# StreamDeck.net
KiCad netlist of a schematic drawn in EAGLE
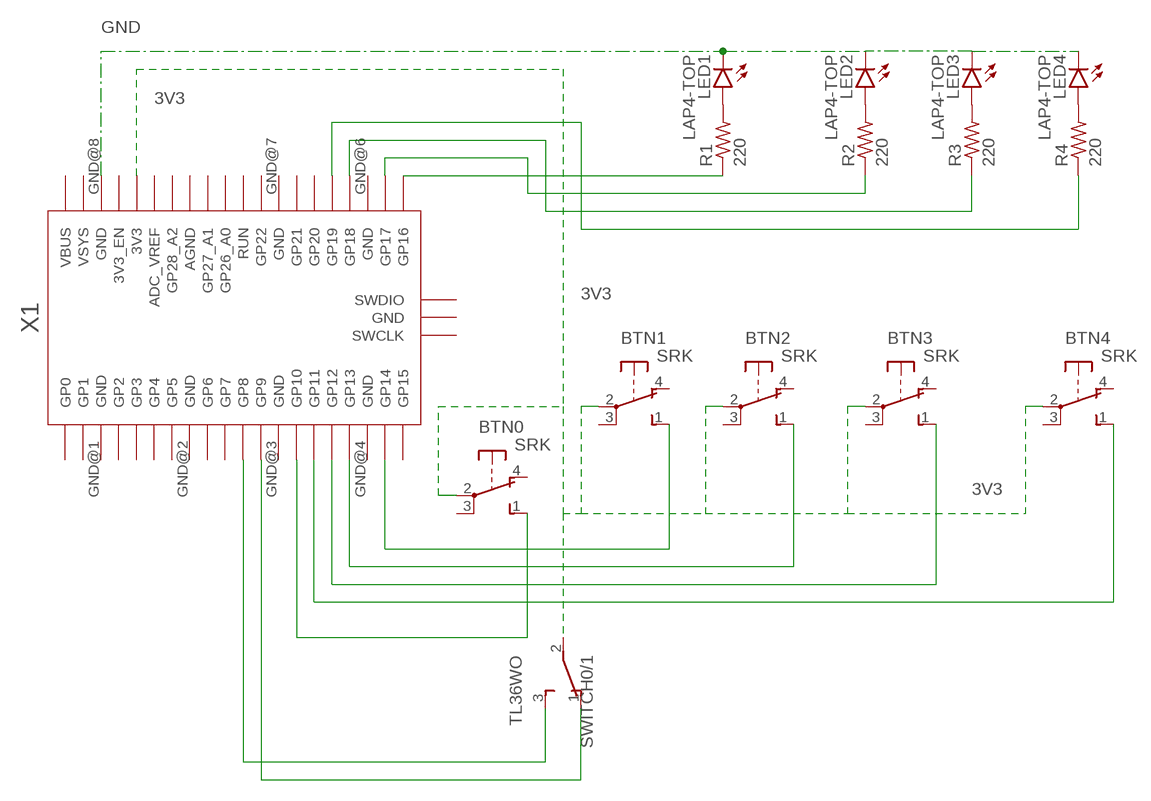
[diagram p0: schematic, sheet 1]

(export (version "E")
  (design (tool "Eeschema 10.0.6"))
  (components
    (comp (ref "BTN0")
      (value "SRK")
      (footprint "eagle-import:SRK")
      (libsource (lib "eagle-import") (part "SRK"))
    )
    (comp (ref "BTN1")
      (value "SRK")
      (footprint "eagle-import:SRK")
      (libsource (lib "eagle-import") (part "SRK"))
    )
    (comp (ref "BTN2")
      (value "SRK")
      (footprint "eagle-import:SRK")
      (libsource (lib "eagle-import") (part "SRK"))
    )
    (comp (ref "BTN3")
      (value "SRK")
      (footprint "eagle-import:SRK")
      (libsource (lib "eagle-import") (part "SRK"))
    )
    (comp (ref "BTN4")
      (value "SRK")
      (footprint "eagle-import:SRK")
      (libsource (lib "eagle-import") (part "SRK"))
    )
    (comp (ref "LED1")
      (value "LAP4-TOP")
      (footprint "eagle-import:P47F-TOP")
      (libsource (lib "eagle-import") (part "P4-TOPLA"))
    )
    (comp (ref "LED2")
      (value "LAP4-TOP")
      (footprint "eagle-import:P47F-TOP")
      (libsource (lib "eagle-import") (part "P4-TOPLA"))
    )
    (comp (ref "LED3")
      (value "LAP4-TOP")
      (footprint "eagle-import:P47F-TOP")
      (libsource (lib "eagle-import") (part "P4-TOPLA"))
    )
    (comp (ref "LED4")
      (value "LAP4-TOP")
      (footprint "eagle-import:P47F-TOP")
      (libsource (lib "eagle-import") (part "P4-TOPLA"))
    )
    (comp (ref "R1")
      (value "220")
      (footprint "eagle-import:0204_5")
      (libsource (lib "eagle-import") (part "R-US_0204/5"))
    )
    (comp (ref "R2")
      (value "220")
      (footprint "eagle-import:0204_5")
      (libsource (lib "eagle-import") (part "R-US_0204/5"))
    )
    (comp (ref "R3")
      (value "220")
      (footprint "eagle-import:0204_5")
      (libsource (lib "eagle-import") (part "R-US_0204/5"))
    )
    (comp (ref "R4")
      (value "220")
      (footprint "eagle-import:0204_5")
      (libsource (lib "eagle-import") (part "R-US_0204/5"))
    )
    (comp (ref "SWITCH0/1")
      (value "TL36WO")
      (footprint "eagle-import:TL3XWO")
      (libsource (lib "eagle-import") (part "TL36WO"))
    )
    (comp (ref "X1")
      (value "RPI_PICO_IG-SMD")
      (footprint "eagle-import:RPI_PICO")
      (libsource (lib "eagle-import") (part "RPI_PICO_IG-SMD"))
    )
  )
  (nets
    (net (code "1") (name "/3V3") (class "Default")
      (node (ref "BTN0") (pin "2") (pinfunction "P_2") (pintype "passive"))
      (node (ref "BTN1") (pin "2") (pinfunction "P_2") (pintype "passive"))
      (node (ref "BTN2") (pin "2") (pinfunction "P_2") (pintype "passive"))
      (node (ref "BTN3") (pin "2") (pinfunction "P_2") (pintype "passive"))
      (node (ref "BTN4") (pin "2") (pinfunction "P_2") (pintype "passive"))
      (node (ref "SWITCH0/1") (pin "2") (pinfunction "P_2") (pintype "passive"))
      (node (ref "X1") (pin "3V3") (pinfunction "3V3_3V3") (pintype "bidirectional"))
    )
    (net (code "2") (name "/GND") (class "Default")
      (node (ref "LED1") (pin "C") (pinfunction "C_C") (pintype "passive"))
      (node (ref "LED2") (pin "C") (pinfunction "C_C") (pintype "passive"))
      (node (ref "LED3") (pin "C") (pinfunction "C_C") (pintype "passive"))
      (node (ref "LED4") (pin "C") (pinfunction "C_C") (pintype "passive"))
      (node (ref "X1") (pin "GND@8") (pinfunction "GND_GND@8") (pintype "bidirectional"))
    )
    (net (code "3") (name "Net-(BTN0-S)") (class "Default")
      (node (ref "BTN0") (pin "1") (pinfunction "S_1") (pintype "passive"))
      (node (ref "X1") (pin "GP10") (pinfunction "GP10_GP10") (pintype "bidirectional"))
    )
    (net (code "4") (name "Net-(BTN1-S)") (class "Default")
      (node (ref "BTN1") (pin "1") (pinfunction "S_1") (pintype "passive"))
      (node (ref "X1") (pin "GP14") (pinfunction "GP14_GP14") (pintype "bidirectional"))
    )
    (net (code "5") (name "Net-(BTN2-S)") (class "Default")
      (node (ref "BTN2") (pin "1") (pinfunction "S_1") (pintype "passive"))
      (node (ref "X1") (pin "GP13") (pinfunction "GP13_GP13") (pintype "bidirectional"))
    )
    (net (code "6") (name "Net-(BTN3-S)") (class "Default")
      (node (ref "BTN3") (pin "1") (pinfunction "S_1") (pintype "passive"))
      (node (ref "X1") (pin "GP12") (pinfunction "GP12_GP12") (pintype "bidirectional"))
    )
    (net (code "7") (name "Net-(BTN4-S)") (class "Default")
      (node (ref "BTN4") (pin "1") (pinfunction "S_1") (pintype "passive"))
      (node (ref "X1") (pin "GP11") (pinfunction "GP11_GP11") (pintype "bidirectional"))
    )
    (net (code "8") (name "Net-(LED1-PadA)") (class "Default")
      (node (ref "LED1") (pin "A") (pinfunction "A_A") (pintype "passive"))
      (node (ref "R1") (pin "2") (pinfunction "2_2") (pintype "passive"))
    )
    (net (code "9") (name "Net-(LED2-PadA)") (class "Default")
      (node (ref "LED2") (pin "A") (pinfunction "A_A") (pintype "passive"))
      (node (ref "R2") (pin "2") (pinfunction "2_2") (pintype "passive"))
    )
    (net (code "10") (name "Net-(LED3-PadA)") (class "Default")
      (node (ref "LED3") (pin "A") (pinfunction "A_A") (pintype "passive"))
      (node (ref "R3") (pin "2") (pinfunction "2_2") (pintype "passive"))
    )
    (net (code "11") (name "Net-(LED4-PadA)") (class "Default")
      (node (ref "LED4") (pin "A") (pinfunction "A_A") (pintype "passive"))
      (node (ref "R4") (pin "2") (pinfunction "2_2") (pintype "passive"))
    )
    (net (code "12") (name "Net-(R1-Pad1)") (class "Default")
      (node (ref "R1") (pin "1") (pinfunction "1_1") (pintype "passive"))
      (node (ref "X1") (pin "GP16") (pinfunction "GP16_GP16") (pintype "bidirectional"))
    )
    (net (code "13") (name "Net-(R2-Pad1)") (class "Default")
      (node (ref "R2") (pin "1") (pinfunction "1_1") (pintype "passive"))
      (node (ref "X1") (pin "GP17") (pinfunction "GP17_GP17") (pintype "bidirectional"))
    )
    (net (code "14") (name "Net-(R3-Pad1)") (class "Default")
      (node (ref "R3") (pin "1") (pinfunction "1_1") (pintype "passive"))
      (node (ref "X1") (pin "GP18") (pinfunction "GP18_GP18") (pintype "bidirectional"))
    )
    (net (code "15") (name "Net-(R4-Pad1)") (class "Default")
      (node (ref "R4") (pin "1") (pinfunction "1_1") (pintype "passive"))
      (node (ref "X1") (pin "GP19") (pinfunction "GP19_GP19") (pintype "bidirectional"))
    )
    (net (code "16") (name "Net-(SWITCH0/1-O)") (class "Default")
      (node (ref "SWITCH0/1") (pin "1") (pinfunction "O_1") (pintype "passive"))
      (node (ref "X1") (pin "GP9") (pinfunction "GP9_GP9") (pintype "bidirectional"))
    )
    (net (code "17") (name "Net-(SWITCH0/1-S)") (class "Default")
      (node (ref "SWITCH0/1") (pin "3") (pinfunction "S_3") (pintype "passive"))
      (node (ref "X1") (pin "GP8") (pinfunction "GP8_GP8") (pintype "bidirectional"))
    )
    (net (code "18") (name "unconnected-(BTN0-O-Pad4)") (class "Default")
      (node (ref "BTN0") (pin "4") (pinfunction "O_4") (pintype "passive"))
    )
    (net (code "19") (name "unconnected-(BTN0-P-Pad3)") (class "Default")
      (node (ref "BTN0") (pin "3") (pinfunction "P_3") (pintype "passive"))
    )
    (net (code "20") (name "unconnected-(BTN1-O-Pad4)") (class "Default")
      (node (ref "BTN1") (pin "4") (pinfunction "O_4") (pintype "passive"))
    )
    (net (code "21") (name "unconnected-(BTN1-P-Pad3)") (class "Default")
      (node (ref "BTN1") (pin "3") (pinfunction "P_3") (pintype "passive"))
    )
    (net (code "22") (name "unconnected-(BTN2-O-Pad4)") (class "Default")
      (node (ref "BTN2") (pin "4") (pinfunction "O_4") (pintype "passive"))
    )
    (net (code "23") (name "unconnected-(BTN2-P-Pad3)") (class "Default")
      (node (ref "BTN2") (pin "3") (pinfunction "P_3") (pintype "passive"))
    )
    (net (code "24") (name "unconnected-(BTN3-O-Pad4)") (class "Default")
      (node (ref "BTN3") (pin "4") (pinfunction "O_4") (pintype "passive"))
    )
    (net (code "25") (name "unconnected-(BTN3-P-Pad3)") (class "Default")
      (node (ref "BTN3") (pin "3") (pinfunction "P_3") (pintype "passive"))
    )
    (net (code "26") (name "unconnected-(BTN4-O-Pad4)") (class "Default")
      (node (ref "BTN4") (pin "4") (pinfunction "O_4") (pintype "passive"))
    )
    (net (code "27") (name "unconnected-(BTN4-P-Pad3)") (class "Default")
      (node (ref "BTN4") (pin "3") (pinfunction "P_3") (pintype "passive"))
    )
    (net (code "28") (name "unconnected-(X1-GND-PadGND@1)") (class "Default")
      (node (ref "X1") (pin "GND@1") (pinfunction "GND_GND@1") (pintype "bidirectional"))
    )
    (net (code "29") (name "unconnected-(X1-GND-PadGND@2)") (class "Default")
      (node (ref "X1") (pin "GND@2") (pinfunction "GND_GND@2") (pintype "bidirectional"))
    )
    (net (code "30") (name "unconnected-(X1-GND-PadGND@3)") (class "Default")
      (node (ref "X1") (pin "GND@3") (pinfunction "GND_GND@3") (pintype "bidirectional"))
    )
    (net (code "31") (name "unconnected-(X1-GND-PadGND@4)") (class "Default")
      (node (ref "X1") (pin "GND@4") (pinfunction "GND_GND@4") (pintype "bidirectional"))
    )
    (net (code "32") (name "unconnected-(X1-GND-PadGND@5)") (class "Default")
      (node (ref "X1") (pin "GND@5") (pinfunction "GND_GND@5") (pintype "bidirectional"))
    )
    (net (code "33") (name "unconnected-(X1-GND-PadGND@6)") (class "Default")
      (node (ref "X1") (pin "GND@6") (pinfunction "GND_GND@6") (pintype "bidirectional"))
    )
    (net (code "34") (name "unconnected-(X1-GND-PadGND@7)") (class "Default")
      (node (ref "X1") (pin "GND@7") (pinfunction "GND_GND@7") (pintype "bidirectional"))
    )
    (net (code "35") (name "unconnected-(X1-Pad3V3_EN)") (class "Default")
      (node (ref "X1") (pin "3V3_EN") (pinfunction "3V3_EN_3V3_EN") (pintype "bidirectional"))
    )
    (net (code "36") (name "unconnected-(X1-PadADC_VREF)") (class "Default")
      (node (ref "X1") (pin "ADC_VREF") (pinfunction "ADC_VREF_ADC_VREF") (pintype "bidirectional"))
    )
    (net (code "37") (name "unconnected-(X1-PadAGND)") (class "Default")
      (node (ref "X1") (pin "AGND") (pinfunction "AGND_AGND") (pintype "bidirectional"))
    )
    (net (code "38") (name "unconnected-(X1-PadGP0)") (class "Default")
      (node (ref "X1") (pin "GP0") (pinfunction "GP0_GP0") (pintype "bidirectional"))
    )
    (net (code "39") (name "unconnected-(X1-PadGP1)") (class "Default")
      (node (ref "X1") (pin "GP1") (pinfunction "GP1_GP1") (pintype "bidirectional"))
    )
    (net (code "40") (name "unconnected-(X1-PadGP2)") (class "Default")
      (node (ref "X1") (pin "GP2") (pinfunction "GP2_GP2") (pintype "bidirectional"))
    )
    (net (code "41") (name "unconnected-(X1-PadGP3)") (class "Default")
      (node (ref "X1") (pin "GP3") (pinfunction "GP3_GP3") (pintype "bidirectional"))
    )
    (net (code "42") (name "unconnected-(X1-PadGP4)") (class "Default")
      (node (ref "X1") (pin "GP4") (pinfunction "GP4_GP4") (pintype "bidirectional"))
    )
    (net (code "43") (name "unconnected-(X1-PadGP5)") (class "Default")
      (node (ref "X1") (pin "GP5") (pinfunction "GP5_GP5") (pintype "bidirectional"))
    )
    (net (code "44") (name "unconnected-(X1-PadGP6)") (class "Default")
      (node (ref "X1") (pin "GP6") (pinfunction "GP6_GP6") (pintype "bidirectional"))
    )
    (net (code "45") (name "unconnected-(X1-PadGP7)") (class "Default")
      (node (ref "X1") (pin "GP7") (pinfunction "GP7_GP7") (pintype "bidirectional"))
    )
    (net (code "46") (name "unconnected-(X1-PadGP15)") (class "Default")
      (node (ref "X1") (pin "GP15") (pinfunction "GP15_GP15") (pintype "bidirectional"))
    )
    (net (code "47") (name "unconnected-(X1-PadGP20)") (class "Default")
      (node (ref "X1") (pin "GP20") (pinfunction "GP20_GP20") (pintype "bidirectional"))
    )
    (net (code "48") (name "unconnected-(X1-PadGP21)") (class "Default")
      (node (ref "X1") (pin "GP21") (pinfunction "GP21_GP21") (pintype "bidirectional"))
    )
    (net (code "49") (name "unconnected-(X1-PadGP22)") (class "Default")
      (node (ref "X1") (pin "GP22") (pinfunction "GP22_GP22") (pintype "bidirectional"))
    )
    (net (code "50") (name "unconnected-(X1-PadGP26_A0)") (class "Default")
      (node (ref "X1") (pin "GP26_A0") (pinfunction "GP26_A0_GP26_A0") (pintype "bidirectional"))
    )
    (net (code "51") (name "unconnected-(X1-PadGP27_A1)") (class "Default")
      (node (ref "X1") (pin "GP27_A1") (pinfunction "GP27_A1_GP27_A1") (pintype "bidirectional"))
    )
    (net (code "52") (name "unconnected-(X1-PadGP28_A2)") (class "Default")
      (node (ref "X1") (pin "GP28_A2") (pinfunction "GP28_A2_GP28_A2") (pintype "bidirectional"))
    )
    (net (code "53") (name "unconnected-(X1-PadRUN)") (class "Default")
      (node (ref "X1") (pin "RUN") (pinfunction "RUN_RUN") (pintype "bidirectional"))
    )
    (net (code "54") (name "unconnected-(X1-PadSWCLK)") (class "Default")
      (node (ref "X1") (pin "SWCLK") (pinfunction "SWCLK_SWCLK") (pintype "bidirectional"))
    )
    (net (code "55") (name "unconnected-(X1-PadSWDIO)") (class "Default")
      (node (ref "X1") (pin "SWDIO") (pinfunction "SWDIO_SWDIO") (pintype "bidirectional"))
    )
    (net (code "56") (name "unconnected-(X1-PadVBUS)") (class "Default")
      (node (ref "X1") (pin "VBUS") (pinfunction "VBUS_VBUS") (pintype "bidirectional"))
    )
    (net (code "57") (name "unconnected-(X1-PadVSYS)") (class "Default")
      (node (ref "X1") (pin "VSYS") (pinfunction "VSYS_VSYS") (pintype "bidirectional"))
    )
  )
)
